# tx.net
KiCad netlist of a schematic drawn in EAGLE
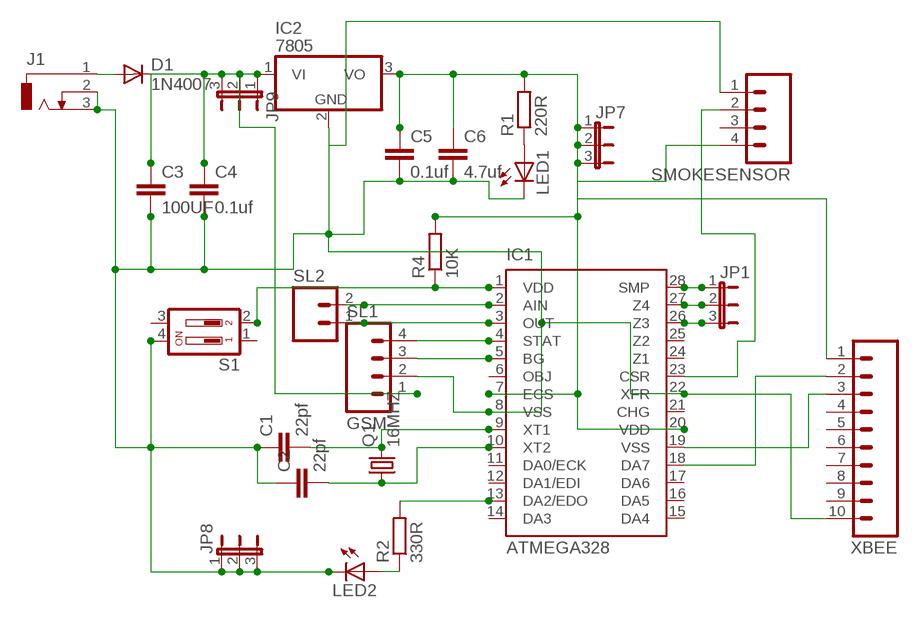
[diagram p0: schematic, sheet 1]

(export (version "E")
  (design (tool "Eeschema 10.0.6"))
  (components
    (comp (ref "C1")
      (value "22pf")
      (footprint "eagle-import:C2.5-2")
      (libsource (lib "eagle-import") (part "C2.5/2"))
    )
    (comp (ref "C2")
      (value "22pf")
      (footprint "eagle-import:C2.5-2")
      (libsource (lib "eagle-import") (part "C2.5/2"))
    )
    (comp (ref "C3")
      (value "100UF")
      (footprint "eagle-import:C2.5-2")
      (libsource (lib "eagle-import") (part "C2.5/2"))
    )
    (comp (ref "C4")
      (value "0.1uf")
      (footprint "eagle-import:C2.5-2")
      (libsource (lib "eagle-import") (part "C2.5/2"))
    )
    (comp (ref "C5")
      (value "0.1uf")
      (footprint "eagle-import:C2.5-2")
      (libsource (lib "eagle-import") (part "C2.5/2"))
    )
    (comp (ref "C6")
      (value "4.7uf")
      (footprint "eagle-import:C2.5-2")
      (libsource (lib "eagle-import") (part "C2.5/2"))
    )
    (comp (ref "D1")
      (value "1N4007")
      (footprint "eagle-import:DO41-10")
      (libsource (lib "eagle-import") (part "1N4004"))
    )
    (comp (ref "IC1")
      (value "ATMEGA328")
      (footprint "eagle-import:DIL28-3")
      (libsource (lib "eagle-import") (part "QT9701BD"))
    )
    (comp (ref "IC2")
      (value "7805")
      (footprint "eagle-import:TO220V")
      (libsource (lib "eagle-import") (part "78TV6"))
    )
    (comp (ref "J1")
      (value "DCJ0303")
      (footprint "eagle-import:DCJ0303")
      (libsource (lib "eagle-import") (part "DCJ0303"))
    )
    (comp (ref "JP1")
      (value "JP2E")
      (footprint "eagle-import:JP2")
      (libsource (lib "eagle-import") (part "JP2E"))
    )
    (comp (ref "JP7")
      (value "JP2E")
      (footprint "eagle-import:JP2")
      (libsource (lib "eagle-import") (part "JP2E"))
    )
    (comp (ref "JP8")
      (value "JP2E")
      (footprint "eagle-import:JP2")
      (libsource (lib "eagle-import") (part "JP2E"))
    )
    (comp (ref "JP9")
      (value "JP2E")
      (footprint "eagle-import:JP2")
      (libsource (lib "eagle-import") (part "JP2E"))
    )
    (comp (ref "LED1")
      (value "LED3MM")
      (footprint "eagle-import:LED3MM")
      (libsource (lib "eagle-import") (part "LED3MM"))
    )
    (comp (ref "LED2")
      (value "LED3MM")
      (footprint "eagle-import:LED3MM")
      (libsource (lib "eagle-import") (part "LED3MM"))
    )
    (comp (ref "Q1")
      (value "16MHZ")
      (footprint "eagle-import:HC49_S")
      (libsource (lib "eagle-import") (part "CRYSTALHC49S"))
    )
    (comp (ref "R1")
      (value "220R")
      (footprint "eagle-import:0207_10")
      (libsource (lib "eagle-import") (part "R-EU_0207/10"))
    )
    (comp (ref "R2")
      (value "330R")
      (footprint "eagle-import:0207_10")
      (libsource (lib "eagle-import") (part "R-EU_0207/10"))
    )
    (comp (ref "R4")
      (value "10K")
      (footprint "eagle-import:0207_10")
      (libsource (lib "eagle-import") (part "R-EU_0207/10"))
    )
    (comp (ref "S1")
      (value "DP02")
      (footprint "eagle-import:DP-02")
      (fields (field (name "MPN") "MCDP02"))
      (libsource (lib "eagle-import") (part "DP02"))
    )
    (comp (ref "SL1")
      (value "GSM")
      (footprint "eagle-import:04P")
      (libsource (lib "eagle-import") (part "M04"))
    )
    (comp (ref "SL2")
      (value "M02")
      (footprint "eagle-import:02P")
      (libsource (lib "eagle-import") (part "M02"))
    )
    (comp (ref "SMOKESENSOR")
      (value "M04")
      (footprint "eagle-import:04P")
      (libsource (lib "eagle-import") (part "M04"))
    )
    (comp (ref "XBEE")
      (value "M10")
      (footprint "eagle-import:10P")
      (libsource (lib "eagle-import") (part "M10"))
    )
  )
  (nets
    (net (code "1") (name "Net-(D1-PadA)") (class "Default")
      (node (ref "D1") (pin "A") (pinfunction "A_A") (pintype "passive"))
      (node (ref "J1") (pin "1") (pinfunction "1_1") (pintype "passive"))
    )
    (net (code "2") (name "Net-(IC1-AIN)") (class "Default")
      (node (ref "IC1") (pin "2") (pinfunction "AIN_2") (pintype "input"))
      (node (ref "SL2") (pin "2") (pinfunction "2_2") (pintype "passive"))
    )
    (net (code "3") (name "Net-(IC1-BG)") (class "Default")
      (node (ref "IC1") (pin "5") (pinfunction "BG_5") (pintype "input"))
      (node (ref "SL1") (pin "3") (pinfunction "3_3") (pintype "passive"))
    )
    (net (code "4") (name "Net-(IC1-CSR)") (class "Default")
      (node (ref "IC1") (pin "23") (pinfunction "CSR_23") (pintype "output"))
      (node (ref "SMOKESENSOR") (pin "2") (pinfunction "2_2") (pintype "passive"))
    )
    (net (code "5") (name "Net-(IC1-DA2{slash}EDO)") (class "Default")
      (node (ref "IC1") (pin "13") (pinfunction "DA2/EDO_13") (pintype "output"))
      (node (ref "R2") (pin "2") (pinfunction "2_2") (pintype "passive"))
    )
    (net (code "6") (name "Net-(IC1-DA7)") (class "Default")
      (node (ref "IC1") (pin "18") (pinfunction "DA7_18") (pintype "output"))
      (node (ref "XBEE") (pin "2") (pinfunction "2_2") (pintype "passive"))
    )
    (net (code "7") (name "Net-(IC1-ECS)") (class "Default")
      (node (ref "C5") (pin "1") (pinfunction "1_1") (pintype "passive"))
      (node (ref "C6") (pin "1") (pinfunction "1_1") (pintype "passive"))
      (node (ref "IC1") (pin "20") (pinfunction "VDD_20") (pintype "input"))
      (node (ref "IC1") (pin "7") (pinfunction "ECS_7") (pintype "output"))
      (node (ref "IC2") (pin "3") (pinfunction "VO_3") (pintype "passive"))
      (node (ref "JP7") (pin "1") (pinfunction "1_1") (pintype "passive"))
      (node (ref "JP7") (pin "2") (pinfunction "2_2") (pintype "passive"))
      (node (ref "JP7") (pin "3") (pinfunction "3_3") (pintype "passive"))
      (node (ref "R1") (pin "2") (pinfunction "2_2") (pintype "passive"))
      (node (ref "R4") (pin "2") (pinfunction "2_2") (pintype "passive"))
      (node (ref "SMOKESENSOR") (pin "4") (pinfunction "4_4") (pintype "passive"))
      (node (ref "XBEE") (pin "1") (pinfunction "1_1") (pintype "passive"))
    )
    (net (code "8") (name "Net-(IC1-OUT)") (class "Default")
      (node (ref "IC1") (pin "3") (pinfunction "OUT_3") (pintype "output"))
      (node (ref "SL2") (pin "1") (pinfunction "1_1") (pintype "passive"))
    )
    (net (code "9") (name "Net-(IC1-SMP)") (class "Default")
      (node (ref "IC1") (pin "28") (pinfunction "SMP_28") (pintype "output"))
      (node (ref "JP1") (pin "1") (pinfunction "1_1") (pintype "passive"))
    )
    (net (code "10") (name "Net-(IC1-STAT)") (class "Default")
      (node (ref "IC1") (pin "4") (pinfunction "STAT_4") (pintype "output"))
      (node (ref "SL1") (pin "4") (pinfunction "4_4") (pintype "passive"))
    )
    (net (code "11") (name "Net-(IC1-VDD-Pad1)") (class "Default")
      (node (ref "IC1") (pin "1") (pinfunction "VDD_1") (pintype "input"))
      (node (ref "R4") (pin "1") (pinfunction "1_1") (pintype "passive"))
      (node (ref "S1") (pin "2") (pinfunction "2_2") (pintype "passive"))
    )
    (net (code "12") (name "Net-(IC1-VSS-Pad19)") (class "Default")
      (node (ref "IC1") (pin "19") (pinfunction "VSS_19") (pintype "input"))
      (node (ref "XBEE") (pin "3") (pinfunction "3_3") (pintype "passive"))
    )
    (net (code "13") (name "Net-(IC1-XFR)") (class "Default")
      (node (ref "C1") (pin "1") (pinfunction "1_1") (pintype "passive"))
      (node (ref "C2") (pin "1") (pinfunction "1_1") (pintype "passive"))
      (node (ref "C3") (pin "2") (pinfunction "2_2") (pintype "passive"))
      (node (ref "C4") (pin "2") (pinfunction "2_2") (pintype "passive"))
      (node (ref "C5") (pin "2") (pinfunction "2_2") (pintype "passive"))
      (node (ref "C6") (pin "2") (pinfunction "2_2") (pintype "passive"))
      (node (ref "IC1") (pin "22") (pinfunction "XFR_22") (pintype "output"))
      (node (ref "IC1") (pin "8") (pinfunction "VSS_8") (pintype "input"))
      (node (ref "IC2") (pin "2") (pinfunction "GND_2") (pintype "passive"))
      (node (ref "J1") (pin "2") (pinfunction "2_2") (pintype "passive"))
      (node (ref "J1") (pin "3") (pinfunction "3_3") (pintype "passive"))
      (node (ref "JP8") (pin "1") (pinfunction "1_1") (pintype "passive"))
      (node (ref "JP8") (pin "2") (pinfunction "2_2") (pintype "passive"))
      (node (ref "JP8") (pin "3") (pinfunction "3_3") (pintype "passive"))
      (node (ref "LED1") (pin "K") (pinfunction "C_K") (pintype "passive"))
      (node (ref "LED2") (pin "K") (pinfunction "C_K") (pintype "passive"))
      (node (ref "S1") (pin "4") (pinfunction "4_4") (pintype "passive"))
      (node (ref "SL1") (pin "2") (pinfunction "2_2") (pintype "passive"))
      (node (ref "SMOKESENSOR") (pin "1") (pinfunction "1_1") (pintype "passive"))
      (node (ref "XBEE") (pin "10") (pinfunction "10_10") (pintype "passive"))
    )
    (net (code "14") (name "Net-(IC1-XT1)") (class "Default")
      (node (ref "C1") (pin "2") (pinfunction "2_2") (pintype "passive"))
      (node (ref "IC1") (pin "9") (pinfunction "XT1_9") (pintype "input"))
      (node (ref "Q1") (pin "2") (pinfunction "2_2") (pintype "passive"))
    )
    (net (code "15") (name "Net-(IC1-XT2)") (class "Default")
      (node (ref "C2") (pin "2") (pinfunction "2_2") (pintype "passive"))
      (node (ref "IC1") (pin "10") (pinfunction "XT2_10") (pintype "output"))
      (node (ref "Q1") (pin "1") (pinfunction "1_1") (pintype "passive"))
    )
    (net (code "16") (name "Net-(IC1-Z3)") (class "Default")
      (node (ref "IC1") (pin "26") (pinfunction "Z3_26") (pintype "output"))
      (node (ref "JP1") (pin "3") (pinfunction "3_3") (pintype "passive"))
    )
    (net (code "17") (name "Net-(IC1-Z4)") (class "Default")
      (node (ref "IC1") (pin "27") (pinfunction "Z4_27") (pintype "output"))
      (node (ref "JP1") (pin "2") (pinfunction "2_2") (pintype "passive"))
    )
    (net (code "18") (name "Net-(IC2-VI)") (class "Default")
      (node (ref "C3") (pin "1") (pinfunction "1_1") (pintype "passive"))
      (node (ref "C4") (pin "1") (pinfunction "1_1") (pintype "passive"))
      (node (ref "D1") (pin "C") (pinfunction "C_C") (pintype "passive"))
      (node (ref "IC2") (pin "1") (pinfunction "VI_1") (pintype "input"))
      (node (ref "JP9") (pin "1") (pinfunction "1_1") (pintype "passive"))
      (node (ref "JP9") (pin "2") (pinfunction "2_2") (pintype "passive"))
      (node (ref "JP9") (pin "3") (pinfunction "3_3") (pintype "passive"))
      (node (ref "SL1") (pin "1") (pinfunction "1_1") (pintype "passive"))
    )
    (net (code "19") (name "Net-(LED1-PadA)") (class "Default")
      (node (ref "LED1") (pin "A") (pinfunction "A_A") (pintype "passive"))
      (node (ref "R1") (pin "1") (pinfunction "1_1") (pintype "passive"))
    )
    (net (code "20") (name "Net-(LED2-PadA)") (class "Default")
      (node (ref "LED2") (pin "A") (pinfunction "A_A") (pintype "passive"))
      (node (ref "R2") (pin "1") (pinfunction "1_1") (pintype "passive"))
    )
    (net (code "21") (name "unconnected-(IC1-CHG-Pad21)") (class "Default")
      (node (ref "IC1") (pin "21") (pinfunction "CHG_21") (pintype "output"))
    )
    (net (code "22") (name "unconnected-(IC1-DA0{slash}ECK-Pad11)") (class "Default")
      (node (ref "IC1") (pin "11") (pinfunction "DA0/ECK_11") (pintype "output"))
    )
    (net (code "23") (name "unconnected-(IC1-DA1{slash}EDI-Pad12)") (class "Default")
      (node (ref "IC1") (pin "12") (pinfunction "DA1/EDI_12") (pintype "output"))
    )
    (net (code "24") (name "unconnected-(IC1-DA3-Pad14)") (class "Default")
      (node (ref "IC1") (pin "14") (pinfunction "DA3_14") (pintype "output"))
    )
    (net (code "25") (name "unconnected-(IC1-DA4-Pad15)") (class "Default")
      (node (ref "IC1") (pin "15") (pinfunction "DA4_15") (pintype "output"))
    )
    (net (code "26") (name "unconnected-(IC1-DA5-Pad16)") (class "Default")
      (node (ref "IC1") (pin "16") (pinfunction "DA5_16") (pintype "output"))
    )
    (net (code "27") (name "unconnected-(IC1-DA6-Pad17)") (class "Default")
      (node (ref "IC1") (pin "17") (pinfunction "DA6_17") (pintype "output"))
    )
    (net (code "28") (name "unconnected-(IC1-OBJ-Pad6)") (class "Default")
      (node (ref "IC1") (pin "6") (pinfunction "OBJ_6") (pintype "input"))
    )
    (net (code "29") (name "unconnected-(IC1-Z1-Pad24)") (class "Default")
      (node (ref "IC1") (pin "24") (pinfunction "Z1_24") (pintype "output"))
    )
    (net (code "30") (name "unconnected-(IC1-Z2-Pad25)") (class "Default")
      (node (ref "IC1") (pin "25") (pinfunction "Z2_25") (pintype "output"))
    )
    (net (code "31") (name "unconnected-(S1-Pad1)") (class "Default")
      (node (ref "S1") (pin "1") (pinfunction "1_1") (pintype "passive"))
    )
    (net (code "32") (name "unconnected-(S1-Pad3)") (class "Default")
      (node (ref "S1") (pin "3") (pinfunction "3_3") (pintype "passive"))
    )
    (net (code "33") (name "unconnected-(SMOKESENSOR-Pad3)") (class "Default")
      (node (ref "SMOKESENSOR") (pin "3") (pinfunction "3_3") (pintype "passive"))
    )
    (net (code "34") (name "unconnected-(XBEE-Pad4)") (class "Default")
      (node (ref "XBEE") (pin "4") (pinfunction "4_4") (pintype "passive"))
    )
    (net (code "35") (name "unconnected-(XBEE-Pad5)") (class "Default")
      (node (ref "XBEE") (pin "5") (pinfunction "5_5") (pintype "passive"))
    )
    (net (code "36") (name "unconnected-(XBEE-Pad6)") (class "Default")
      (node (ref "XBEE") (pin "6") (pinfunction "6_6") (pintype "passive"))
    )
    (net (code "37") (name "unconnected-(XBEE-Pad7)") (class "Default")
      (node (ref "XBEE") (pin "7") (pinfunction "7_7") (pintype "passive"))
    )
    (net (code "38") (name "unconnected-(XBEE-Pad8)") (class "Default")
      (node (ref "XBEE") (pin "8") (pinfunction "8_8") (pintype "passive"))
    )
    (net (code "39") (name "unconnected-(XBEE-Pad9)") (class "Default")
      (node (ref "XBEE") (pin "9") (pinfunction "9_9") (pintype "passive"))
    )
  )
)
